# 03_SCH-03.net
KiCad netlist of a schematic drawn in Altium Designer
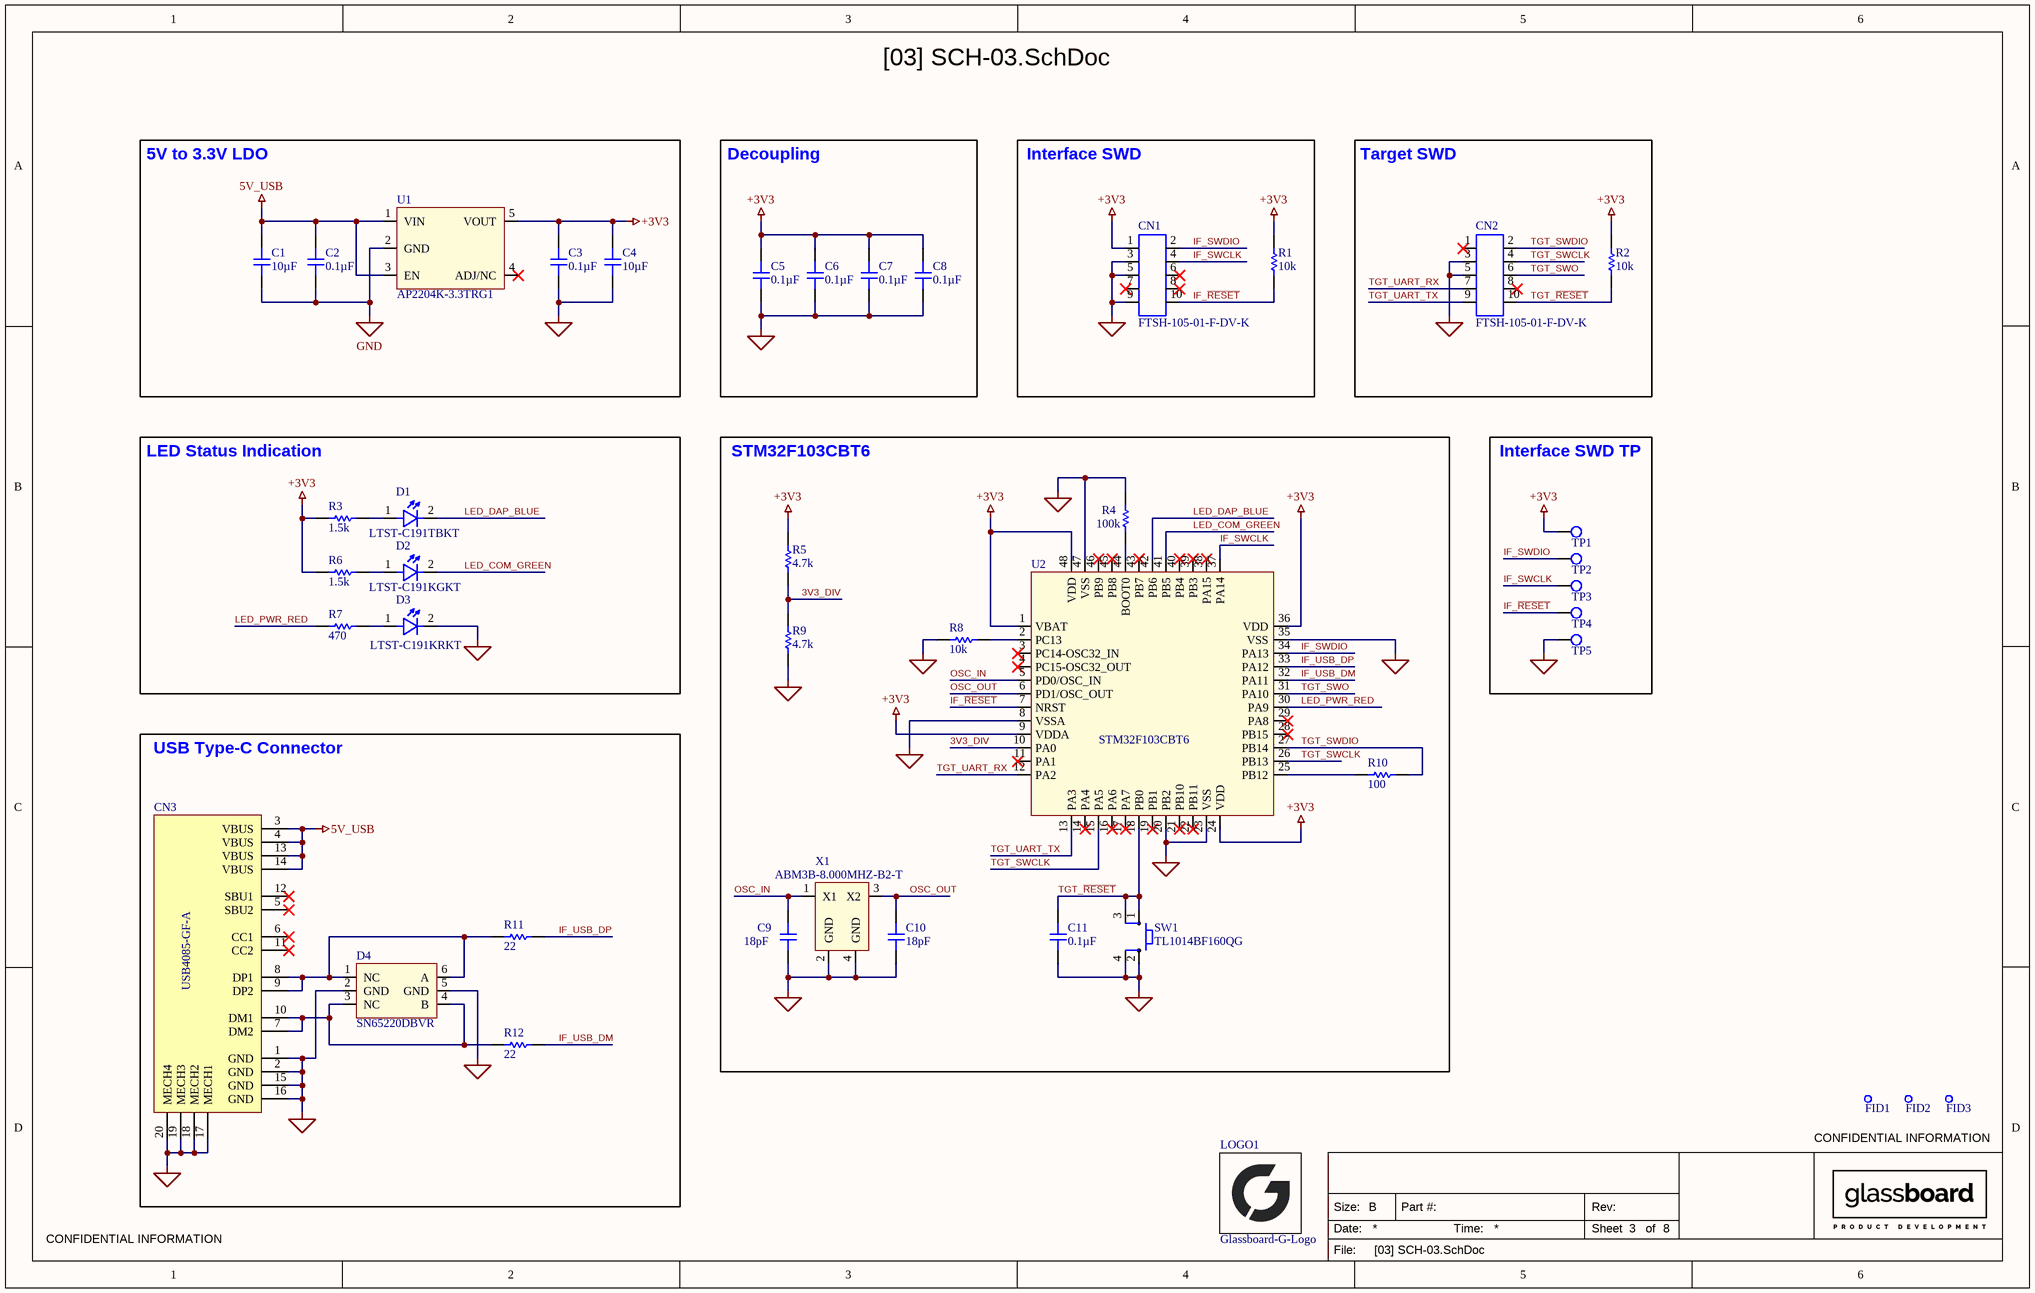
[diagram p0: [03] SCH-03.SchDoc]

(export (version "E")
  (design (tool "Eeschema 10.0.6"))
  (components
    (comp (ref "C1")
      (value "10µF")
      (footprint "CAPC0402(1005)70_L")
      (description "CAP CER 10UF 6.3V X5R 0402")
      (fields
        (field (name "PART NUMBER") "CC0402MRX5R5BB106")
        (field (name "TOLERANCE") "0.2")
        (field (name "PUBLISHER") "Randy Parmerlee")
      )
      (libsource (lib "Glassboard Component Database") (part "Capacitor - Non Polarized"))
    )
    (comp (ref "C2")
      (value "0.1µF")
      (footprint "CAPC0402(1005)70_L")
      (description "CAP CER 0.1UF 10V X5R 0402")
      (fields
        (field (name "PART NUMBER") "CGA2B2X5R1A104M050BA")
        (field (name "TOLERANCE") "0.2")
        (field (name "PUBLISHER") "Drew Westrick")
      )
      (libsource (lib "Glassboard Component Database") (part "Capacitor - Non Polarized"))
    )
    (comp (ref "C3")
      (value "0.1µF")
      (footprint "CAPC0402(1005)70_L")
      (description "CAP CER 0.1UF 10V X5R 0402")
      (fields
        (field (name "PART NUMBER") "CGA2B2X5R1A104M050BA")
        (field (name "TOLERANCE") "0.2")
        (field (name "PUBLISHER") "Drew Westrick")
      )
      (libsource (lib "Glassboard Component Database") (part "Capacitor - Non Polarized"))
    )
    (comp (ref "C4")
      (value "10µF")
      (footprint "CAPC0402(1005)70_L")
      (description "CAP CER 10UF 6.3V X5R 0402")
      (fields
        (field (name "PART NUMBER") "CC0402MRX5R5BB106")
        (field (name "TOLERANCE") "0.2")
        (field (name "PUBLISHER") "Randy Parmerlee")
      )
      (libsource (lib "Glassboard Component Database") (part "Capacitor - Non Polarized"))
    )
    (comp (ref "C5")
      (value "0.1µF")
      (footprint "CAPC0402(1005)70_L")
      (description "CAP CER 0.1UF 10V X5R 0402")
      (fields
        (field (name "PART NUMBER") "CGA2B2X5R1A104M050BA")
        (field (name "TOLERANCE") "0.2")
        (field (name "PUBLISHER") "Drew Westrick")
      )
      (libsource (lib "Glassboard Component Database") (part "Capacitor - Non Polarized"))
    )
    (comp (ref "C6")
      (value "0.1µF")
      (footprint "CAPC0402(1005)70_L")
      (description "CAP CER 0.1UF 10V X5R 0402")
      (fields
        (field (name "PART NUMBER") "CGA2B2X5R1A104M050BA")
        (field (name "TOLERANCE") "0.2")
        (field (name "PUBLISHER") "Drew Westrick")
      )
      (libsource (lib "Glassboard Component Database") (part "Capacitor - Non Polarized"))
    )
    (comp (ref "C7")
      (value "0.1µF")
      (footprint "CAPC0402(1005)70_L")
      (description "CAP CER 0.1UF 10V X5R 0402")
      (fields
        (field (name "PART NUMBER") "CGA2B2X5R1A104M050BA")
        (field (name "TOLERANCE") "0.2")
        (field (name "PUBLISHER") "Drew Westrick")
      )
      (libsource (lib "Glassboard Component Database") (part "Capacitor - Non Polarized"))
    )
    (comp (ref "C8")
      (value "0.1µF")
      (footprint "CAPC0402(1005)70_L")
      (description "CAP CER 0.1UF 10V X5R 0402")
      (fields
        (field (name "PART NUMBER") "CGA2B2X5R1A104M050BA")
        (field (name "TOLERANCE") "0.2")
        (field (name "PUBLISHER") "Drew Westrick")
      )
      (libsource (lib "Glassboard Component Database") (part "Capacitor - Non Polarized"))
    )
    (comp (ref "C9")
      (value "18pF")
      (footprint "CAPC0402(1005)70_L")
      (description "CAP CER 18PF 50V C0G/NPO 0402")
      (fields
        (field (name "PART NUMBER") "CC0402JRNPO9BN180")
        (field (name "TOLERANCE") "0.05")
        (field (name "PUBLISHER") "Randy Parmerlee")
      )
      (libsource (lib "Glassboard Component Database") (part "Capacitor - Non Polarized"))
    )
    (comp (ref "C10")
      (value "18pF")
      (footprint "CAPC0402(1005)70_L")
      (description "CAP CER 18PF 50V C0G/NPO 0402")
      (fields
        (field (name "PART NUMBER") "CC0402JRNPO9BN180")
        (field (name "TOLERANCE") "0.05")
        (field (name "PUBLISHER") "Randy Parmerlee")
      )
      (libsource (lib "Glassboard Component Database") (part "Capacitor - Non Polarized"))
    )
    (comp (ref "C11")
      (value "0.1µF")
      (footprint "CAPC0402(1005)70_L")
      (description "CAP CER 0.1UF 10V X5R 0402")
      (fields
        (field (name "PART NUMBER") "CGA2B2X5R1A104M050BA")
        (field (name "TOLERANCE") "0.2")
        (field (name "PUBLISHER") "Drew Westrick")
      )
      (libsource (lib "Glassboard Component Database") (part "Capacitor - Non Polarized"))
    )
    (comp (ref "CN1")
      (value "FTSH-105-01-F-DV-K")
      (footprint "FTSH-105-01-F-DV-K")
      (description "CONN HEADER 10POS DUAL .05\" SMD")
      (fields
        (field (name "MANUFACTURER") "Samtec Inc")
        (field (name "DISTRIBUTOR 1 PART NUMBER") "SAM8796-ND")
        (field (name "PUBLISHER") "Drew Westrick")
      )
      (libsource (lib "Glassboard Component Database") (part "CONN HEADER 10 POS DUAL ROW"))
    )
    (comp (ref "CN2")
      (value "FTSH-105-01-F-DV-K")
      (footprint "FTSH-105-01-F-DV-K")
      (description "CONN HEADER 10POS DUAL .05\" SMD")
      (fields
        (field (name "MANUFACTURER") "Samtec Inc")
        (field (name "DISTRIBUTOR 1 PART NUMBER") "SAM8796-ND")
        (field (name "PUBLISHER") "Drew Westrick")
      )
      (libsource (lib "Glassboard Component Database") (part "CONN HEADER 10 POS DUAL ROW"))
    )
    (comp (ref "CN3")
      (value "USB4085-GF-A")
      (footprint "USB4085-GF-A")
      (description "CONN RCPT USB2.0 TYPEC 16POS")
      (fields
        (field (name "MANUFACTURER") "GCT")
        (field (name "DISTRIBUTOR 1 PART NUMBER") "2073-USB4085-GF-ACT-ND")
        (field (name "PUBLISHER") "Stephen Murphy")
      )
      (libsource (lib "Glassboard Component Database") (part "USB4085-GF-A"))
    )
    (comp (ref "D1")
      (value "LTST-C191TBKT")
      (footprint "LTST-C191KGKT")
      (description "LED BLUE CLEAR 0603 SMD")
      (fields
        (field (name "MANUFACTURER") "Lite-On Inc")
        (field (name "DISTRIBUTOR 1 PART NUMBER") "160-1647-1-ND")
        (field (name "PUBLISHER") "Randy Parmerlee")
      )
      (libsource (lib "Glassboard Component Database") (part "Standard LED"))
    )
    (comp (ref "D2")
      (value "LTST-C191KGKT")
      (footprint "LTST-C191KGKT")
      (description "LED GREEN CLEAR THIN 0603 SMD")
      (fields
        (field (name "MANUFACTURER") "Lite-On Inc")
        (field (name "DISTRIBUTOR 1 PART NUMBER") "160-1446-1-ND")
        (field (name "PUBLISHER") "Randy Parmerlee")
      )
      (libsource (lib "Glassboard Component Database") (part "Standard LED"))
    )
    (comp (ref "D3")
      (value "LTST-C191KRKT")
      (footprint "LTST-C191KGKT")
      (description "LED RED CLEAR 0603 SMD")
      (fields
        (field (name "MANUFACTURER") "Lite-On Inc")
        (field (name "DISTRIBUTOR 1 PART NUMBER") "160-1447-1-ND")
        (field (name "PUBLISHER") "Randy Parmerlee")
      )
      (libsource (lib "Glassboard Component Database") (part "Standard LED"))
    )
    (comp (ref "D4")
      (value "SN65220DBVR")
      (footprint "SN65220DBVR-L")
      (description "IC SINGLE USB PORT TVS SOT-23-6")
      (fields
        (field (name "VOLTAGE") "5V")
        (field (name "MANUFACTURER") "Texas Instruments")
        (field (name "PUBLISHER") "Randy Parmerlee")
      )
      (libsource (lib "Glassboard Component Database") (part "SN65220DBVR"))
    )
    (comp (ref "FID1")
      (value "FID")
      (footprint "fid_30mil")
      (description "Surface Mount Fiducials")
      (fields (field (name "PART NUMBER") "Fiducial") (field (name "PUBLISHER") "Randy Parmerlee"))
      (libsource (lib "Glassboard Component Database") (part "Fiducial"))
    )
    (comp (ref "FID2")
      (value "FID")
      (footprint "fid_30mil")
      (description "Surface Mount Fiducials")
      (fields (field (name "PART NUMBER") "Fiducial") (field (name "PUBLISHER") "Randy Parmerlee"))
      (libsource (lib "Glassboard Component Database") (part "Fiducial"))
    )
    (comp (ref "FID3")
      (value "FID")
      (footprint "fid_30mil")
      (description "Surface Mount Fiducials")
      (fields (field (name "PART NUMBER") "Fiducial") (field (name "PUBLISHER") "Randy Parmerlee"))
      (libsource (lib "Glassboard Component Database") (part "Fiducial"))
    )
    (comp (ref "LOGO1") (value "Glassboard-G-Logo") (libsource (lib "logos") (part "Glassboard-G-Logo")))
    (comp (ref "R1")
      (value "10k")
      (footprint "RESC0402(1005)_L")
      (description "RES SMD 10K OHM 1% 1/16W 0402")
      (fields
        (field (name "PART NUMBER") "RC0402FR-0710KL")
        (field (name "TOLERANCE") "0.01")
        (field (name "PUBLISHER") "Randy Parmerlee")
      )
      (libsource (lib "Glassboard Component Database") (part "Resistor - Standard"))
    )
    (comp (ref "R2")
      (value "10k")
      (footprint "RESC0402(1005)_L")
      (description "RES SMD 10K OHM 1% 1/16W 0402")
      (fields
        (field (name "PART NUMBER") "RC0402FR-0710KL")
        (field (name "TOLERANCE") "0.01")
        (field (name "PUBLISHER") "Randy Parmerlee")
      )
      (libsource (lib "Glassboard Component Database") (part "Resistor - Standard"))
    )
    (comp (ref "R3")
      (value "1.5k")
      (footprint "RESC0402(1005)_L")
      (description "RES SMD 1.5K OHM 1% 1/10W 0402")
      (fields
        (field (name "PART NUMBER") "ERJ-2RKF1501X")
        (field (name "TOLERANCE") "0.01")
        (field (name "PUBLISHER") "Drew Westrick")
      )
      (libsource (lib "Glassboard Component Database") (part "Resistor - Standard"))
    )
    (comp (ref "R4")
      (value "100k")
      (footprint "RESC0402(1005)_L")
      (description "RES SMD 100K OHM 1% 1/16W 0402")
      (fields
        (field (name "PART NUMBER") "RC0402FR-07100KL")
        (field (name "TOLERANCE") "0.01")
        (field (name "PUBLISHER") "Randy Parmerlee")
      )
      (libsource (lib "Glassboard Component Database") (part "Resistor - Standard"))
    )
    (comp (ref "R5")
      (value "4.7k")
      (footprint "RESC0402(1005)_L")
      (description "RES SMD 4.7K OHM 1% 1/10W 0402")
      (fields
        (field (name "PART NUMBER") "ERJ-2RKF4701X")
        (field (name "TOLERANCE") "0.01")
        (field (name "PUBLISHER") "Drew Westrick")
      )
      (libsource (lib "Glassboard Component Database") (part "Resistor - Standard"))
    )
    (comp (ref "R6")
      (value "1.5k")
      (footprint "RESC0402(1005)_L")
      (description "RES SMD 1.5K OHM 1% 1/10W 0402")
      (fields
        (field (name "PART NUMBER") "ERJ-2RKF1501X")
        (field (name "TOLERANCE") "0.01")
        (field (name "PUBLISHER") "Drew Westrick")
      )
      (libsource (lib "Glassboard Component Database") (part "Resistor - Standard"))
    )
    (comp (ref "R7")
      (value "470")
      (footprint "RESC0402(1005)_L")
      (description "RES SMD 470 OHM 1% 1/10W 0402")
      (fields
        (field (name "PART NUMBER") "ERJ-2RKF4700X")
        (field (name "TOLERANCE") "0.01")
        (field (name "PUBLISHER") "Drew Westrick")
      )
      (libsource (lib "Glassboard Component Database") (part "Resistor - Standard"))
    )
    (comp (ref "R8")
      (value "10k")
      (footprint "RESC0402(1005)_L")
      (description "RES SMD 10K OHM 1% 1/16W 0402")
      (fields
        (field (name "PART NUMBER") "RC0402FR-0710KL")
        (field (name "TOLERANCE") "0.01")
        (field (name "PUBLISHER") "Randy Parmerlee")
      )
      (libsource (lib "Glassboard Component Database") (part "Resistor - Standard"))
    )
    (comp (ref "R9")
      (value "4.7k")
      (footprint "RESC0402(1005)_L")
      (description "RES SMD 4.7K OHM 1% 1/10W 0402")
      (fields
        (field (name "PART NUMBER") "ERJ-2RKF4701X")
        (field (name "TOLERANCE") "0.01")
        (field (name "PUBLISHER") "Drew Westrick")
      )
      (libsource (lib "Glassboard Component Database") (part "Resistor - Standard"))
    )
    (comp (ref "R10")
      (value "100")
      (footprint "RESC0402(1005)_L")
      (description "RES SMD 100 OHM 1% 1/16W 0402")
      (fields
        (field (name "PART NUMBER") "RC0402FR-07100RL")
        (field (name "TOLERANCE") "0.01")
        (field (name "PUBLISHER") "Randy Parmerlee")
      )
      (libsource (lib "Glassboard Component Database") (part "Resistor - Standard"))
    )
    (comp (ref "R11")
      (value "22")
      (footprint "RESC0402(1005)_L")
      (description "RES SMD 22 OHM 1% 1/16W 0402")
      (fields
        (field (name "PART NUMBER") "RC0402FR-0722RL")
        (field (name "TOLERANCE") "0.01")
        (field (name "PUBLISHER") "Randy Parmerlee")
      )
      (libsource (lib "Glassboard Component Database") (part "Resistor - Standard"))
    )
    (comp (ref "R12")
      (value "22")
      (footprint "RESC0402(1005)_L")
      (description "RES SMD 22 OHM 1% 1/16W 0402")
      (fields
        (field (name "PART NUMBER") "RC0402FR-0722RL")
        (field (name "TOLERANCE") "0.01")
        (field (name "PUBLISHER") "Randy Parmerlee")
      )
      (libsource (lib "Glassboard Component Database") (part "Resistor - Standard"))
    )
    (comp (ref "SW1")
      (value "TL1014BF160QG")
      (footprint "TL1014BF160QG")
      (description "SWITCH TACTILE SPST-NO 0.05A 12V")
      (fields
        (field (name "MANUFACTURER") "E-Switch")
        (field (name "DISTRIBUTOR 1 PART NUMBER") "EG5042CT-ND")
        (field (name "PUBLISHER") "Randy Parmerlee")
      )
      (libsource (lib "Glassboard Component Database") (part "TL1014BF160QG"))
    )
    (comp (ref "TP1")
      (value "TESTFIXTURE_16MM")
      (footprint "TESTFIXTURE_16MM")
      (description "TEST POINT ROUND 1.6mm")
      (fields (field (name "MANUFACTURER") "GlassBoard") (field (name "PUBLISHER") "Ethan Harmon"))
      (libsource (lib "Glassboard Component Database") (part "SINGLE_TP"))
    )
    (comp (ref "TP2")
      (value "TESTFIXTURE_16MM")
      (footprint "TESTFIXTURE_16MM")
      (description "TEST POINT ROUND 1.6mm")
      (fields (field (name "MANUFACTURER") "GlassBoard") (field (name "PUBLISHER") "Ethan Harmon"))
      (libsource (lib "Glassboard Component Database") (part "SINGLE_TP"))
    )
    (comp (ref "TP3")
      (value "TESTFIXTURE_16MM")
      (footprint "TESTFIXTURE_16MM")
      (description "TEST POINT ROUND 1.6mm")
      (fields (field (name "MANUFACTURER") "GlassBoard") (field (name "PUBLISHER") "Ethan Harmon"))
      (libsource (lib "Glassboard Component Database") (part "SINGLE_TP"))
    )
    (comp (ref "TP4")
      (value "TESTFIXTURE_16MM")
      (footprint "TESTFIXTURE_16MM")
      (description "TEST POINT ROUND 1.6mm")
      (fields (field (name "MANUFACTURER") "GlassBoard") (field (name "PUBLISHER") "Ethan Harmon"))
      (libsource (lib "Glassboard Component Database") (part "SINGLE_TP"))
    )
    (comp (ref "TP5")
      (value "TESTFIXTURE_16MM")
      (footprint "TESTFIXTURE_16MM")
      (description "TEST POINT ROUND 1.6mm")
      (fields (field (name "MANUFACTURER") "GlassBoard") (field (name "PUBLISHER") "Ethan Harmon"))
      (libsource (lib "Glassboard Component Database") (part "SINGLE_TP"))
    )
    (comp (ref "U1")
      (value "AP2204K-3.3TRG1")
      (footprint "AP2204K-3.3TRG1_L")
      (description "IC REG LDO 3.3V 0.15A SOT25")
      (fields
        (field (name "VOLTAGE") "24V")
        (field (name "MANUFACTURER") "Diodes Incorporated")
        (field (name "PUBLISHER") "Randy Parmerlee")
      )
      (libsource (lib "Glassboard Component Database") (part "AP2204K-3.3TRG1"))
    )
    (comp (ref "U2")
      (value "STM32F103CBT6")
      (footprint "STM32F103CBT6")
      (description "IC MCU 32BIT 128KB FLASH 48LQFP")
      (fields
        (field (name "VOLTAGE") "2V ~ 3.6V")
        (field (name "MANUFACTURER") "STMicroelectronics")
        (field (name "PUBLISHER") "Stephen Murphy")
      )
      (libsource (lib "Glassboard Component Database") (part "STM32F103CBT6"))
    )
    (comp (ref "X1")
      (value "ABM3B-8.000MHZ-B2-T")
      (footprint "ABM3B-8.000MHZ-B2-T")
      (description "CRYSTAL 8.0000MHZ 18PF SMD")
      (fields
        (field (name "MANUFACTURER") "Abracon LLC")
        (field (name "DISTRIBUTOR 1 PART NUMBER") "535-9720-1-ND")
        (field (name "PUBLISHER") "Randy Parmerlee")
      )
      (libsource (lib "Glassboard Component Database") (part "ABM3B-8.000MHZ-B2-T"))
    )
  )
  (nets
    (net (code "1") (name "+3V3") (class "Default")
      (node (ref "C3") (pin "2") (pinfunction "2_2") (pintype "passive"))
      (node (ref "C4") (pin "2") (pinfunction "2_2") (pintype "passive"))
      (node (ref "C5") (pin "2") (pinfunction "2_2") (pintype "passive"))
      (node (ref "C6") (pin "2") (pinfunction "2_2") (pintype "passive"))
      (node (ref "C7") (pin "2") (pinfunction "2_2") (pintype "passive"))
      (node (ref "C8") (pin "2") (pinfunction "2_2") (pintype "passive"))
      (node (ref "CN1") (pin "1") (pinfunction "1_1") (pintype "passive"))
      (node (ref "R1") (pin "2") (pinfunction "2_2") (pintype "passive"))
      (node (ref "R2") (pin "2") (pinfunction "2_2") (pintype "passive"))
      (node (ref "R3") (pin "1") (pinfunction "1_1") (pintype "passive"))
      (node (ref "R5") (pin "2") (pinfunction "2_2") (pintype "passive"))
      (node (ref "R6") (pin "1") (pinfunction "1_1") (pintype "passive"))
      (node (ref "TP1") (pin "1") (pintype "passive"))
      (node (ref "U1") (pin "5") (pinfunction "VOUT_5") (pintype "passive"))
      (node (ref "U2") (pin "1") (pinfunction "VBAT_1") (pintype "passive"))
      (node (ref "U2") (pin "24") (pinfunction "VDD_24") (pintype "passive"))
      (node (ref "U2") (pin "36") (pinfunction "VDD_36") (pintype "passive"))
      (node (ref "U2") (pin "48") (pinfunction "VDD_48") (pintype "passive"))
      (node (ref "U2") (pin "9") (pinfunction "VDDA_9") (pintype "passive"))
    )
    (net (code "2") (name "/3V3_DIV") (class "Default")
      (node (ref "R5") (pin "1") (pinfunction "1_1") (pintype "passive"))
      (node (ref "R9") (pin "2") (pinfunction "2_2") (pintype "passive"))
      (node (ref "U2") (pin "10") (pinfunction "PA0_10") (pintype "passive"))
    )
    (net (code "3") (name "/IF_SWCLK") (class "Default")
      (node (ref "CN1") (pin "4") (pinfunction "4_4") (pintype "passive"))
      (node (ref "TP3") (pin "1") (pintype "passive"))
      (node (ref "U2") (pin "37") (pinfunction "PA14_37") (pintype "passive"))
    )
    (net (code "4") (name "/IF_SWDIO") (class "Default")
      (node (ref "CN1") (pin "2") (pinfunction "2_2") (pintype "passive"))
      (node (ref "TP2") (pin "1") (pintype "passive"))
      (node (ref "U2") (pin "34") (pinfunction "PA13_34") (pintype "passive"))
    )
    (net (code "5") (name "/IF_USB_DM") (class "Default")
      (node (ref "R12") (pin "2") (pinfunction "2_2") (pintype "passive"))
      (node (ref "U2") (pin "32") (pinfunction "PA11_32") (pintype "passive"))
    )
    (net (code "6") (name "/IF_USB_DP") (class "Default")
      (node (ref "R11") (pin "2") (pinfunction "2_2") (pintype "passive"))
      (node (ref "U2") (pin "33") (pinfunction "PA12_33") (pintype "passive"))
    )
    (net (code "7") (name "/IF_~{RESET}") (class "Default")
      (node (ref "CN1") (pin "10") (pinfunction "10_10") (pintype "passive"))
      (node (ref "R1") (pin "1") (pinfunction "1_1") (pintype "passive"))
      (node (ref "TP4") (pin "1") (pintype "passive"))
      (node (ref "U2") (pin "7") (pinfunction "NRST_7") (pintype "passive"))
    )
    (net (code "8") (name "/LED_COM_GREEN") (class "Default")
      (node (ref "D2") (pin "2") (pinfunction "2_2") (pintype "passive"))
      (node (ref "U2") (pin "41") (pinfunction "PB5_41") (pintype "passive"))
    )
    (net (code "9") (name "/LED_DAP_BLUE") (class "Default")
      (node (ref "D1") (pin "2") (pinfunction "2_2") (pintype "passive"))
      (node (ref "U2") (pin "42") (pinfunction "PB6_42") (pintype "passive"))
    )
    (net (code "10") (name "/LED_PWR_RED") (class "Default")
      (node (ref "R7") (pin "1") (pinfunction "1_1") (pintype "passive"))
      (node (ref "U2") (pin "30") (pinfunction "PA9_30") (pintype "passive"))
    )
    (net (code "11") (name "/OSC_IN") (class "Default")
      (node (ref "C9") (pin "2") (pinfunction "2_2") (pintype "passive"))
      (node (ref "U2") (pin "5") (pinfunction "PD0/OSC_IN_5") (pintype "passive"))
      (node (ref "X1") (pin "1") (pinfunction "X1_1") (pintype "passive"))
    )
    (net (code "12") (name "/OSC_OUT") (class "Default")
      (node (ref "C10") (pin "2") (pinfunction "2_2") (pintype "passive"))
      (node (ref "U2") (pin "6") (pinfunction "PD1/OSC_OUT_6") (pintype "passive"))
      (node (ref "X1") (pin "3") (pinfunction "X2_3") (pintype "passive"))
    )
    (net (code "13") (name "/TGT_SWCLK") (class "Default")
      (node (ref "CN2") (pin "4") (pinfunction "4_4") (pintype "passive"))
      (node (ref "U2") (pin "15") (pinfunction "PA5_15") (pintype "passive"))
      (node (ref "U2") (pin "26") (pinfunction "PB13_26") (pintype "passive"))
    )
    (net (code "14") (name "/TGT_SWDIO") (class "Default")
      (node (ref "CN2") (pin "2") (pinfunction "2_2") (pintype "passive"))
      (node (ref "R10") (pin "2") (pinfunction "2_2") (pintype "passive"))
      (node (ref "U2") (pin "27") (pinfunction "PB14_27") (pintype "passive"))
    )
    (net (code "15") (name "/TGT_SWO") (class "Default")
      (node (ref "CN2") (pin "6") (pinfunction "6_6") (pintype "passive"))
      (node (ref "U2") (pin "31") (pinfunction "PA10_31") (pintype "passive"))
    )
    (net (code "16") (name "/TGT_UART_RX") (class "Default")
      (node (ref "CN2") (pin "7") (pinfunction "7_7") (pintype "passive"))
      (node (ref "U2") (pin "12") (pinfunction "PA2_12") (pintype "passive"))
    )
    (net (code "17") (name "/TGT_UART_TX") (class "Default")
      (node (ref "CN2") (pin "9") (pinfunction "9_9") (pintype "passive"))
      (node (ref "U2") (pin "13") (pinfunction "PA3_13") (pintype "passive"))
    )
    (net (code "18") (name "/TGT_~{RESET}") (class "Default")
      (node (ref "C11") (pin "2") (pinfunction "2_2") (pintype "passive"))
      (node (ref "CN2") (pin "10") (pinfunction "10_10") (pintype "passive"))
      (node (ref "R2") (pin "1") (pinfunction "1_1") (pintype "passive"))
      (node (ref "SW1") (pin "1") (pinfunction "1_1") (pintype "passive"))
      (node (ref "SW1") (pin "3") (pinfunction "3_3") (pintype "passive"))
      (node (ref "U2") (pin "18") (pinfunction "PB0_18") (pintype "passive"))
    )
    (net (code "19") (name "5V_USB") (class "Default")
      (node (ref "C1") (pin "2") (pinfunction "2_2") (pintype "passive"))
      (node (ref "C2") (pin "2") (pinfunction "2_2") (pintype "passive"))
      (node (ref "CN3") (pin "13") (pinfunction "VBUS_13") (pintype "passive"))
      (node (ref "CN3") (pin "14") (pinfunction "VBUS_14") (pintype "passive"))
      (node (ref "CN3") (pin "3") (pinfunction "VBUS_3") (pintype "passive"))
      (node (ref "CN3") (pin "4") (pinfunction "VBUS_4") (pintype "passive"))
      (node (ref "U1") (pin "1") (pinfunction "VIN_1") (pintype "passive"))
      (node (ref "U1") (pin "3") (pinfunction "EN_3") (pintype "passive"))
    )
    (net (code "20") (name "GND") (class "Default")
      (node (ref "C1") (pin "1") (pinfunction "1_1") (pintype "passive"))
      (node (ref "C10") (pin "1") (pinfunction "1_1") (pintype "passive"))
      (node (ref "C11") (pin "1") (pinfunction "1_1") (pintype "passive"))
      (node (ref "C2") (pin "1") (pinfunction "1_1") (pintype "passive"))
      (node (ref "C3") (pin "1") (pinfunction "1_1") (pintype "passive"))
      (node (ref "C4") (pin "1") (pinfunction "1_1") (pintype "passive"))
      (node (ref "C5") (pin "1") (pinfunction "1_1") (pintype "passive"))
      (node (ref "C6") (pin "1") (pinfunction "1_1") (pintype "passive"))
      (node (ref "C7") (pin "1") (pinfunction "1_1") (pintype "passive"))
      (node (ref "C8") (pin "1") (pinfunction "1_1") (pintype "passive"))
      (node (ref "C9") (pin "1") (pinfunction "1_1") (pintype "passive"))
      (node (ref "CN1") (pin "3") (pinfunction "3_3") (pintype "passive"))
      (node (ref "CN1") (pin "5") (pinfunction "5_5") (pintype "passive"))
      (node (ref "CN1") (pin "9") (pinfunction "9_9") (pintype "passive"))
      (node (ref "CN2") (pin "3") (pinfunction "3_3") (pintype "passive"))
      (node (ref "CN2") (pin "5") (pinfunction "5_5") (pintype "passive"))
      (node (ref "CN3") (pin "1") (pinfunction "GND_1") (pintype "passive"))
      (node (ref "CN3") (pin "15") (pinfunction "GND_15") (pintype "passive"))
      (node (ref "CN3") (pin "16") (pinfunction "GND_16") (pintype "passive"))
      (node (ref "CN3") (pin "17") (pinfunction "MECH1_17") (pintype "passive"))
      (node (ref "CN3") (pin "18") (pinfunction "MECH2_18") (pintype "passive"))
      (node (ref "CN3") (pin "19") (pinfunction "MECH3_19") (pintype "passive"))
      (node (ref "CN3") (pin "2") (pinfunction "GND_2") (pintype "passive"))
      (node (ref "CN3") (pin "20") (pinfunction "MECH4_20") (pintype "passive"))
      (node (ref "D3") (pin "2") (pinfunction "2_2") (pintype "passive"))
      (node (ref "D4") (pin "2") (pinfunction "GND_2") (pintype "passive"))
      (node (ref "D4") (pin "5") (pinfunction "GND_5") (pintype "passive"))
      (node (ref "R4") (pin "2") (pinfunction "2_2") (pintype "passive"))
      (node (ref "R8") (pin "1") (pinfunction "1_1") (pintype "passive"))
      (node (ref "R9") (pin "1") (pinfunction "1_1") (pintype "passive"))
      (node (ref "SW1") (pin "2") (pinfunction "2_2") (pintype "passive"))
      (node (ref "SW1") (pin "4") (pinfunction "4_4") (pintype "passive"))
      (node (ref "TP5") (pin "1") (pintype "passive"))
      (node (ref "U1") (pin "2") (pinfunction "GND_2") (pintype "passive"))
      (node (ref "U2") (pin "20") (pinfunction "PB2_20") (pintype "passive"))
      (node (ref "U2") (pin "23") (pinfunction "VSS_23") (pintype "passive"))
      (node (ref "U2") (pin "35") (pinfunction "VSS_35") (pintype "passive"))
      (node (ref "U2") (pin "47") (pinfunction "VSS_47") (pintype "passive"))
      (node (ref "U2") (pin "8") (pinfunction "VSSA_8") (pintype "passive"))
      (node (ref "X1") (pin "2") (pinfunction "GND_2") (pintype "passive"))
      (node (ref "X1") (pin "4") (pinfunction "GND_4") (pintype "passive"))
    )
    (net (code "21") (name "Net-(CN3-DM1)") (class "Default")
      (node (ref "CN3") (pin "10") (pinfunction "DM1_10") (pintype "passive"))
      (node (ref "CN3") (pin "7") (pinfunction "DM2_7") (pintype "passive"))
      (node (ref "D4") (pin "3") (pinfunction "NC_3") (pintype "passive"))
      (node (ref "D4") (pin "4") (pinfunction "B_4") (pintype "passive"))
      (node (ref "R12") (pin "1") (pinfunction "1_1") (pintype "passive"))
    )
    (net (code "22") (name "Net-(CN3-DP1)") (class "Default")
      (node (ref "CN3") (pin "8") (pinfunction "DP1_8") (pintype "passive"))
      (node (ref "CN3") (pin "9") (pinfunction "DP2_9") (pintype "passive"))
      (node (ref "D4") (pin "1") (pinfunction "NC_1") (pintype "passive"))
      (node (ref "D4") (pin "6") (pinfunction "A_6") (pintype "passive"))
      (node (ref "R11") (pin "1") (pinfunction "1_1") (pintype "passive"))
    )
    (net (code "23") (name "Net-(D1-Pad1)") (class "Default")
      (node (ref "D1") (pin "1") (pinfunction "1_1") (pintype "passive"))
      (node (ref "R3") (pin "2") (pinfunction "2_2") (pintype "passive"))
    )
    (net (code "24") (name "Net-(D2-Pad1)") (class "Default")
      (node (ref "D2") (pin "1") (pinfunction "1_1") (pintype "passive"))
      (node (ref "R6") (pin "2") (pinfunction "2_2") (pintype "passive"))
    )
    (net (code "25") (name "Net-(D3-Pad1)") (class "Default")
      (node (ref "D3") (pin "1") (pinfunction "1_1") (pintype "passive"))
      (node (ref "R7") (pin "2") (pinfunction "2_2") (pintype "passive"))
    )
    (net (code "26") (name "Net-(U2-BOOT0)") (class "Default")
      (node (ref "R4") (pin "1") (pinfunction "1_1") (pintype "passive"))
      (node (ref "U2") (pin "44") (pinfunction "BOOT0_44") (pintype "passive"))
    )
    (net (code "27") (name "Net-(U2-PB12)") (class "Default")
      (node (ref "R10") (pin "1") (pinfunction "1_1") (pintype "passive"))
      (node (ref "U2") (pin "25") (pinfunction "PB12_25") (pintype "passive"))
    )
    (net (code "28") (name "Net-(U2-PC13)") (class "Default")
      (node (ref "R8") (pin "2") (pinfunction "2_2") (pintype "passive"))
      (node (ref "U2") (pin "2") (pinfunction "PC13_2") (pintype "passive"))
    )
    (net (code "29") (name "unconnected-(CN1-Pad6)") (class "Default")
      (node (ref "CN1") (pin "6") (pinfunction "6_6") (pintype "passive+no_connect"))
    )
    (net (code "30") (name "unconnected-(CN1-Pad7)") (class "Default")
      (node (ref "CN1") (pin "7") (pinfunction "7_7") (pintype "passive+no_connect"))
    )
    (net (code "31") (name "unconnected-(CN1-Pad8)") (class "Default")
      (node (ref "CN1") (pin "8") (pinfunction "8_8") (pintype "passive+no_connect"))
    )
    (net (code "32") (name "unconnected-(CN2-Pad1)") (class "Default")
      (node (ref "CN2") (pin "1") (pinfunction "1_1") (pintype "passive+no_connect"))
    )
    (net (code "33") (name "unconnected-(CN2-Pad8)") (class "Default")
      (node (ref "CN2") (pin "8") (pinfunction "8_8") (pintype "passive+no_connect"))
    )
    (net (code "34") (name "unconnected-(CN3-CC1-Pad6)") (class "Default")
      (node (ref "CN3") (pin "6") (pinfunction "CC1_6") (pintype "passive+no_connect"))
    )
    (net (code "35") (name "unconnected-(CN3-CC2-Pad11)") (class "Default")
      (node (ref "CN3") (pin "11") (pinfunction "CC2_11") (pintype "passive+no_connect"))
    )
    (net (code "36") (name "unconnected-(CN3-SBU1-Pad12)") (class "Default")
      (node (ref "CN3") (pin "12") (pinfunction "SBU1_12") (pintype "passive+no_connect"))
    )
    (net (code "37") (name "unconnected-(CN3-SBU2-Pad5)") (class "Default")
      (node (ref "CN3") (pin "5") (pinfunction "SBU2_5") (pintype "passive+no_connect"))
    )
    (net (code "38") (name "unconnected-(FID1-Pad0)") (class "Default")
      (node (ref "FID1") (pin "0") (pinfunction "0_0") (pintype "passive"))
    )
    (net (code "39") (name "unconnected-(FID2-Pad0)") (class "Default")
      (node (ref "FID2") (pin "0") (pinfunction "0_0") (pintype "passive"))
    )
    (net (code "40") (name "unconnected-(FID3-Pad0)") (class "Default")
      (node (ref "FID3") (pin "0") (pinfunction "0_0") (pintype "passive"))
    )
    (net (code "41") (name "unconnected-(U1-ADJ{slash}NC-Pad4)") (class "Default")
      (node (ref "U1") (pin "4") (pinfunction "ADJ/NC_4") (pintype "passive+no_connect"))
    )
    (net (code "42") (name "unconnected-(U2-PA1-Pad11)") (class "Default")
      (node (ref "U2") (pin "11") (pinfunction "PA1_11") (pintype "passive+no_connect"))
    )
    (net (code "43") (name "unconnected-(U2-PA4-Pad14)") (class "Default")
      (node (ref "U2") (pin "14") (pinfunction "PA4_14") (pintype "passive+no_connect"))
    )
    (net (code "44") (name "unconnected-(U2-PA6-Pad16)") (class "Default")
      (node (ref "U2") (pin "16") (pinfunction "PA6_16") (pintype "passive+no_connect"))
    )
    (net (code "45") (name "unconnected-(U2-PA7-Pad17)") (class "Default")
      (node (ref "U2") (pin "17") (pinfunction "PA7_17") (pintype "passive+no_connect"))
    )
    (net (code "46") (name "unconnected-(U2-PA8-Pad29)") (class "Default")
      (node (ref "U2") (pin "29") (pinfunction "PA8_29") (pintype "passive+no_connect"))
    )
    (net (code "47") (name "unconnected-(U2-PA15-Pad38)") (class "Default")
      (node (ref "U2") (pin "38") (pinfunction "PA15_38") (pintype "passive+no_connect"))
    )
    (net (code "48") (name "unconnected-(U2-PB1-Pad19)") (class "Default")
      (node (ref "U2") (pin "19") (pinfunction "PB1_19") (pintype "passive+no_connect"))
    )
    (net (code "49") (name "unconnected-(U2-PB3-Pad39)") (class "Default")
      (node (ref "U2") (pin "39") (pinfunction "PB3_39") (pintype "passive+no_connect"))
    )
    (net (code "50") (name "unconnected-(U2-PB4-Pad40)") (class "Default")
      (node (ref "U2") (pin "40") (pinfunction "PB4_40") (pintype "passive+no_connect"))
    )
    (net (code "51") (name "unconnected-(U2-PB7-Pad43)") (class "Default")
      (node (ref "U2") (pin "43") (pinfunction "PB7_43") (pintype "passive+no_connect"))
    )
    (net (code "52") (name "unconnected-(U2-PB8-Pad45)") (class "Default")
      (node (ref "U2") (pin "45") (pinfunction "PB8_45") (pintype "passive+no_connect"))
    )
    (net (code "53") (name "unconnected-(U2-PB9-Pad46)") (class "Default")
      (node (ref "U2") (pin "46") (pinfunction "PB9_46") (pintype "passive+no_connect"))
    )
    (net (code "54") (name "unconnected-(U2-PB10-Pad21)") (class "Default")
      (node (ref "U2") (pin "21") (pinfunction "PB10_21") (pintype "passive+no_connect"))
    )
    (net (code "55") (name "unconnected-(U2-PB11-Pad22)") (class "Default")
      (node (ref "U2") (pin "22") (pinfunction "PB11_22") (pintype "passive+no_connect"))
    )
    (net (code "56") (name "unconnected-(U2-PB15-Pad28)") (class "Default")
      (node (ref "U2") (pin "28") (pinfunction "PB15_28") (pintype "passive+no_connect"))
    )
    (net (code "57") (name "unconnected-(U2-PC14-OSC32_IN-Pad3)") (class "Default")
      (node (ref "U2") (pin "3") (pinfunction "PC14-OSC32_IN_3") (pintype "passive+no_connect"))
    )
    (net (code "58") (name "unconnected-(U2-PC15-OSC32_OUT-Pad4)") (class "Default")
      (node (ref "U2") (pin "4") (pinfunction "PC15-OSC32_OUT_4") (pintype "passive+no_connect"))
    )
  )
)
